# monitor-one-proto-card-v0_0_2.net
KiCad netlist of a schematic drawn in EAGLE
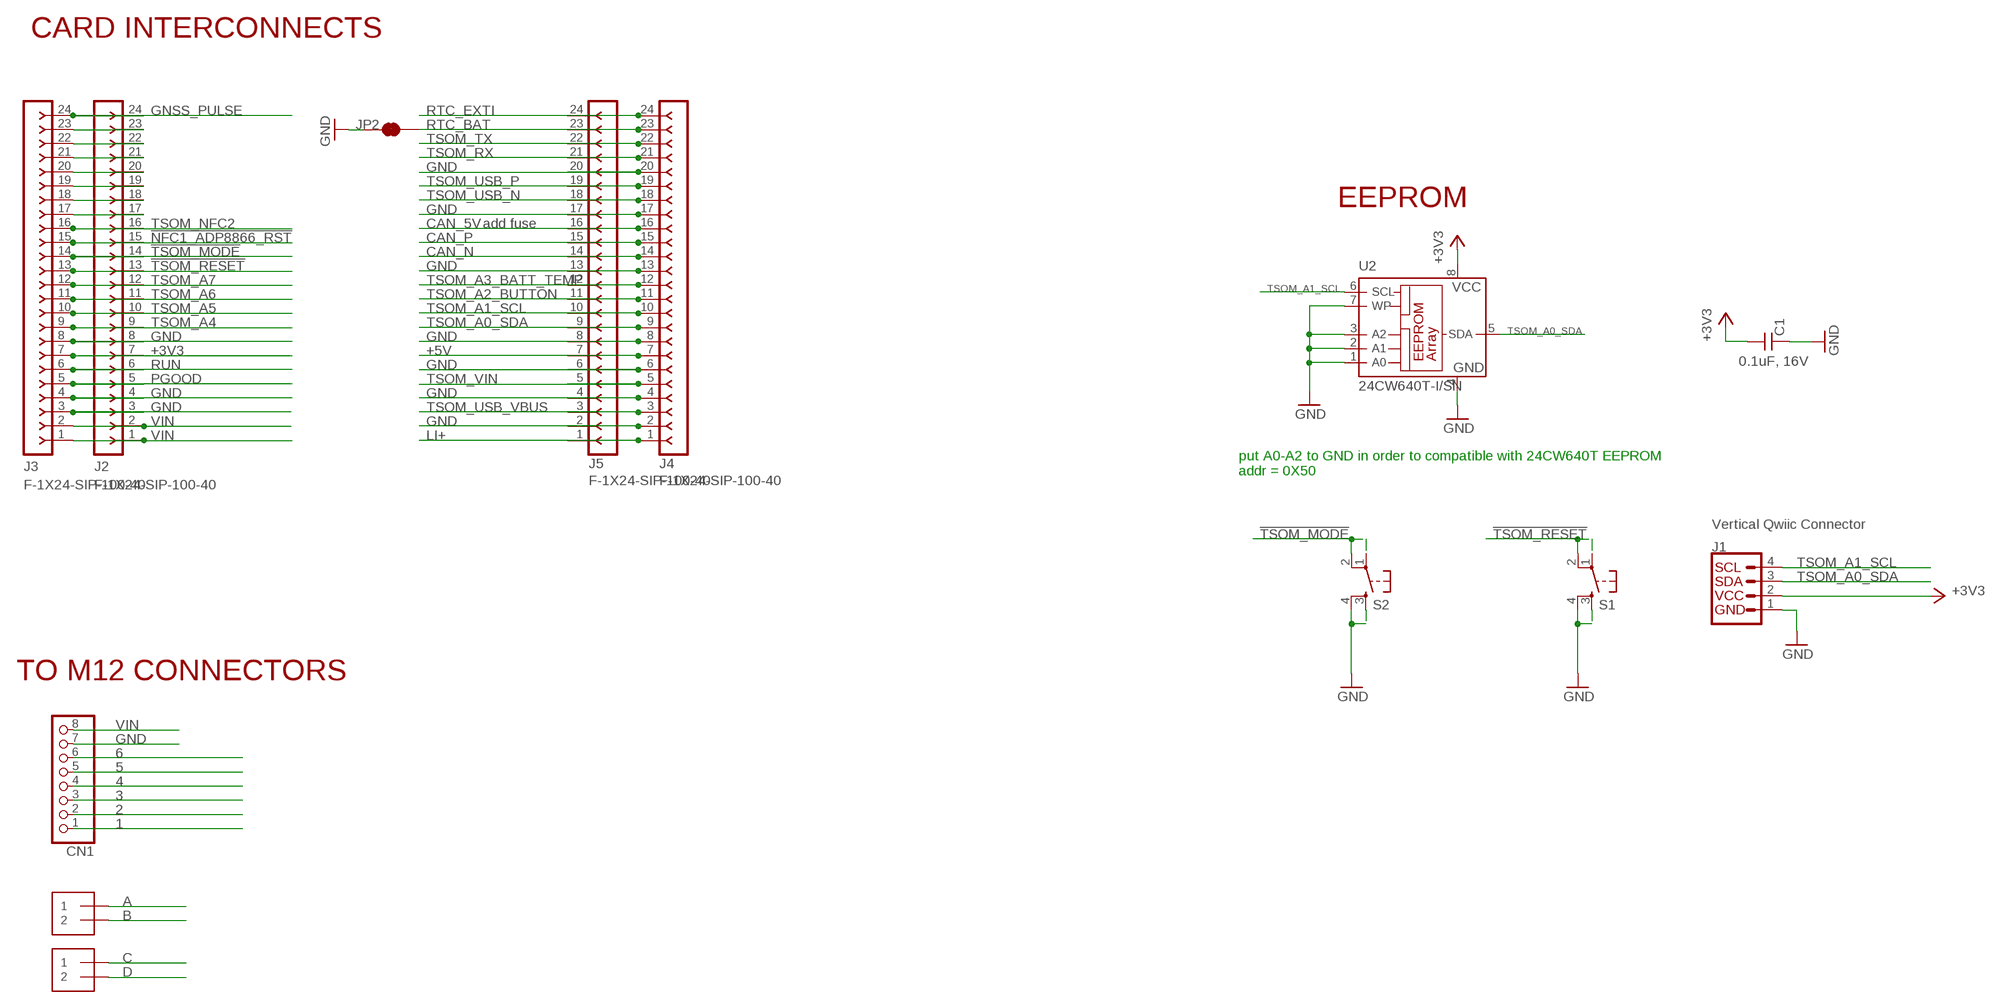
[diagram p0: schematic, sheet 1]

(export (version "E")
  (design (tool "Eeschema 10.0.6"))
  (components
    (comp (ref "C1")
      (value "0.1uF, 16V")
      (footprint "eagle-import:C0603_P")
      (fields (field (name "MFG") "FENGHUA") (field (name "MPN") "0603B104K160NT"))
      (libsource (lib "eagle-import") (part "CAP_06030.1UF_16V_"))
    )
    (comp (ref "CN1")
      (value "JST_8PIN")
      (footprint "eagle-import:JSTPH8")
      (libsource (lib "eagle-import") (part "JST_8PIN"))
    )
    (comp (ref "J1")
      (value "Vertical Qwiic Connector")
      (footprint "eagle-import:JST04_1MM_VERT")
      (libsource (lib "eagle-import") (part "QWIIC_CONNECTOR"))
    )
    (comp (ref "J2")
      (value "F-1X24-SIP-100-40")
      (footprint "eagle-import:SIP-100-24-40")
      (libsource (lib "eagle-import") (part "F-1X24-SIP-100-40"))
    )
    (comp (ref "J3")
      (value "F-1X24-SIP-100-40")
      (footprint "eagle-import:SIP-100-24-40")
      (libsource (lib "eagle-import") (part "F-1X24-SIP-100-40"))
    )
    (comp (ref "J4")
      (value "F-1X24-SIP-100-40")
      (footprint "eagle-import:SIP-100-24-40")
      (libsource (lib "eagle-import") (part "F-1X24-SIP-100-40"))
    )
    (comp (ref "J5")
      (value "F-1X24-SIP-100-40")
      (footprint "eagle-import:SIP-100-24-40")
      (libsource (lib "eagle-import") (part "F-1X24-SIP-100-40"))
    )
    (comp (ref "J8")
      (value "1X2-3.5MM")
      (footprint "eagle-import:1X2-3.5MM")
      (libsource (lib "eagle-import") (part "1X2-3.5MM"))
    )
    (comp (ref "J9")
      (value "1X2-3.5MM")
      (footprint "eagle-import:1X2-3.5MM")
      (libsource (lib "eagle-import") (part "1X2-3.5MM"))
    )
    (comp (ref "JP2")
      (value "JUMPER-SMT_2_NC_TRACE_NO-SILK")
      (footprint "eagle-import:SMT-JUMPER_2_NC_TRACE_NO-SILK")
      (libsource (lib "eagle-import") (part "JUMPER-SMT_2_NC_TRACE_NO-SILK"))
    )
    (comp (ref "S1")
      (value "TAC_SWITCHSMD")
      (footprint "eagle-import:TACTILE_SWITCH_SMD")
      (libsource (lib "eagle-import") (part "TAC_SWITCHSMD"))
    )
    (comp (ref "S2")
      (value "TAC_SWITCHSMD")
      (footprint "eagle-import:TACTILE_SWITCH_SMD")
      (libsource (lib "eagle-import") (part "TAC_SWITCHSMD"))
    )
    (comp (ref "U2")
      (value "24CW640T-I/SN")
      (footprint "eagle-import:SO-08")
      (fields (field (name "MF") "MICROCHIP") (field (name "MPN") "24AA01/SN"))
      (libsource (lib "eagle-import") (part "24SNAA01"))
    )
  )
  (nets
    (net (code "1") (name "+3V3") (class "Default")
      (node (ref "C1") (pin "1") (pinfunction "1_1") (pintype "bidirectional"))
      (node (ref "J1") (pin "2") (pinfunction "2_2") (pintype "power_in"))
      (node (ref "J2") (pin "7") (pinfunction "7_7") (pintype "passive"))
      (node (ref "J3") (pin "7") (pinfunction "7_7") (pintype "passive"))
      (node (ref "U2") (pin "8") (pinfunction "VCC_8") (pintype "power_in"))
    )
    (net (code "2") (name "/+5V") (class "Default")
      (node (ref "J4") (pin "7") (pinfunction "7_7") (pintype "passive"))
      (node (ref "J5") (pin "7") (pinfunction "7_7") (pintype "passive"))
    )
    (net (code "3") (name "/1") (class "Default")
      (node (ref "CN1") (pin "1") (pinfunction "1_1") (pintype "passive"))
    )
    (net (code "4") (name "/2") (class "Default")
      (node (ref "CN1") (pin "2") (pinfunction "2_2") (pintype "passive"))
    )
    (net (code "5") (name "/3") (class "Default")
      (node (ref "CN1") (pin "3") (pinfunction "3_3") (pintype "passive"))
    )
    (net (code "6") (name "/4") (class "Default")
      (node (ref "CN1") (pin "4") (pinfunction "4_4") (pintype "passive"))
    )
    (net (code "7") (name "/5") (class "Default")
      (node (ref "CN1") (pin "5") (pinfunction "5_5") (pintype "passive"))
    )
    (net (code "8") (name "/6") (class "Default")
      (node (ref "CN1") (pin "6") (pinfunction "6_6") (pintype "passive"))
    )
    (net (code "9") (name "/A") (class "Default")
      (node (ref "J8") (pin "1") (pinfunction "1_1") (pintype "passive"))
    )
    (net (code "10") (name "/B") (class "Default")
      (node (ref "J8") (pin "2") (pinfunction "2_2") (pintype "passive"))
    )
    (net (code "11") (name "/C") (class "Default")
      (node (ref "J9") (pin "1") (pinfunction "1_1") (pintype "passive"))
    )
    (net (code "12") (name "/CAN_5V") (class "Default")
      (node (ref "J4") (pin "16") (pinfunction "16_16") (pintype "passive"))
      (node (ref "J5") (pin "16") (pinfunction "16_16") (pintype "passive"))
    )
    (net (code "13") (name "/CAN_N") (class "Default")
      (node (ref "J4") (pin "14") (pinfunction "14_14") (pintype "passive"))
      (node (ref "J5") (pin "14") (pinfunction "14_14") (pintype "passive"))
    )
    (net (code "14") (name "/CAN_P") (class "Default")
      (node (ref "J4") (pin "15") (pinfunction "15_15") (pintype "passive"))
      (node (ref "J5") (pin "15") (pinfunction "15_15") (pintype "passive"))
    )
    (net (code "15") (name "/D") (class "Default")
      (node (ref "J9") (pin "2") (pinfunction "2_2") (pintype "passive"))
    )
    (net (code "16") (name "/GNSS_PULSE") (class "Default")
      (node (ref "J2") (pin "24") (pinfunction "24_24") (pintype "passive"))
      (node (ref "J3") (pin "24") (pinfunction "24_24") (pintype "passive"))
    )
    (net (code "17") (name "/LI+") (class "Default")
      (node (ref "J4") (pin "1") (pinfunction "1_1") (pintype "passive"))
      (node (ref "J5") (pin "1") (pinfunction "1_1") (pintype "passive"))
    )
    (net (code "18") (name "/PGOOD") (class "Default")
      (node (ref "J2") (pin "5") (pinfunction "5_5") (pintype "passive"))
      (node (ref "J3") (pin "5") (pinfunction "5_5") (pintype "passive"))
    )
    (net (code "19") (name "/RTC_BAT") (class "Default")
      (node (ref "J4") (pin "23") (pinfunction "23_23") (pintype "passive"))
      (node (ref "J5") (pin "23") (pinfunction "23_23") (pintype "passive"))
      (node (ref "JP2") (pin "2") (pinfunction "2_2") (pintype "passive"))
    )
    (net (code "20") (name "/RTC_EXTI") (class "Default")
      (node (ref "J4") (pin "24") (pinfunction "24_24") (pintype "passive"))
      (node (ref "J5") (pin "24") (pinfunction "24_24") (pintype "passive"))
    )
    (net (code "21") (name "/RUN") (class "Default")
      (node (ref "J2") (pin "6") (pinfunction "6_6") (pintype "passive"))
      (node (ref "J3") (pin "6") (pinfunction "6_6") (pintype "passive"))
    )
    (net (code "22") (name "/TSOM_A0_SDA") (class "Default")
      (node (ref "J1") (pin "3") (pinfunction "3_3") (pintype "passive"))
      (node (ref "J4") (pin "9") (pinfunction "9_9") (pintype "passive"))
      (node (ref "J5") (pin "9") (pinfunction "9_9") (pintype "passive"))
      (node (ref "U2") (pin "5") (pinfunction "SDA_5") (pintype "bidirectional"))
    )
    (net (code "23") (name "/TSOM_A1_SCL") (class "Default")
      (node (ref "J1") (pin "4") (pinfunction "4_4") (pintype "passive"))
      (node (ref "J4") (pin "10") (pinfunction "10_10") (pintype "passive"))
      (node (ref "J5") (pin "10") (pinfunction "10_10") (pintype "passive"))
      (node (ref "U2") (pin "6") (pinfunction "SCL_6") (pintype "input"))
    )
    (net (code "24") (name "/TSOM_A2_BUTTON") (class "Default")
      (node (ref "J4") (pin "11") (pinfunction "11_11") (pintype "passive"))
      (node (ref "J5") (pin "11") (pinfunction "11_11") (pintype "passive"))
    )
    (net (code "25") (name "/TSOM_A3_BATT_TEMP") (class "Default")
      (node (ref "J4") (pin "12") (pinfunction "12_12") (pintype "passive"))
      (node (ref "J5") (pin "12") (pinfunction "12_12") (pintype "passive"))
    )
    (net (code "26") (name "/TSOM_A4") (class "Default")
      (node (ref "J2") (pin "9") (pinfunction "9_9") (pintype "passive"))
      (node (ref "J3") (pin "9") (pinfunction "9_9") (pintype "passive"))
    )
    (net (code "27") (name "/TSOM_A5") (class "Default")
      (node (ref "J2") (pin "10") (pinfunction "10_10") (pintype "passive"))
      (node (ref "J3") (pin "10") (pinfunction "10_10") (pintype "passive"))
    )
    (net (code "28") (name "/TSOM_A6") (class "Default")
      (node (ref "J2") (pin "11") (pinfunction "11_11") (pintype "passive"))
      (node (ref "J3") (pin "11") (pinfunction "11_11") (pintype "passive"))
    )
    (net (code "29") (name "/TSOM_A7") (class "Default")
      (node (ref "J2") (pin "12") (pinfunction "12_12") (pintype "passive"))
      (node (ref "J3") (pin "12") (pinfunction "12_12") (pintype "passive"))
    )
    (net (code "30") (name "/TSOM_NFC2") (class "Default")
      (node (ref "J2") (pin "16") (pinfunction "16_16") (pintype "passive"))
      (node (ref "J3") (pin "16") (pinfunction "16_16") (pintype "passive"))
    )
    (net (code "31") (name "/TSOM_RX") (class "Default")
      (node (ref "J4") (pin "21") (pinfunction "21_21") (pintype "passive"))
      (node (ref "J5") (pin "21") (pinfunction "21_21") (pintype "passive"))
    )
    (net (code "32") (name "/TSOM_TX") (class "Default")
      (node (ref "J4") (pin "22") (pinfunction "22_22") (pintype "passive"))
      (node (ref "J5") (pin "22") (pinfunction "22_22") (pintype "passive"))
    )
    (net (code "33") (name "/TSOM_USB_N") (class "Default")
      (node (ref "J4") (pin "18") (pinfunction "18_18") (pintype "passive"))
      (node (ref "J5") (pin "18") (pinfunction "18_18") (pintype "passive"))
    )
    (net (code "34") (name "/TSOM_USB_P") (class "Default")
      (node (ref "J4") (pin "19") (pinfunction "19_19") (pintype "passive"))
      (node (ref "J5") (pin "19") (pinfunction "19_19") (pintype "passive"))
    )
    (net (code "35") (name "/TSOM_USB_VBUS") (class "Default")
      (node (ref "J4") (pin "3") (pinfunction "3_3") (pintype "passive"))
      (node (ref "J5") (pin "3") (pinfunction "3_3") (pintype "passive"))
    )
    (net (code "36") (name "/TSOM_VIN") (class "Default")
      (node (ref "J4") (pin "5") (pinfunction "5_5") (pintype "passive"))
      (node (ref "J5") (pin "5") (pinfunction "5_5") (pintype "passive"))
    )
    (net (code "37") (name "/VIN") (class "Default")
      (node (ref "CN1") (pin "8") (pinfunction "8_8") (pintype "passive"))
      (node (ref "J2") (pin "1") (pinfunction "1_1") (pintype "passive"))
      (node (ref "J2") (pin "2") (pinfunction "2_2") (pintype "passive"))
      (node (ref "J3") (pin "1") (pinfunction "1_1") (pintype "passive"))
      (node (ref "J3") (pin "2") (pinfunction "2_2") (pintype "passive"))
    )
    (net (code "38") (name "/~{NFC1_ADP8866_RST}") (class "Default")
      (node (ref "J2") (pin "15") (pinfunction "15_15") (pintype "passive"))
      (node (ref "J3") (pin "15") (pinfunction "15_15") (pintype "passive"))
    )
    (net (code "39") (name "/~{TSOM_MODE}") (class "Default")
      (node (ref "J2") (pin "14") (pinfunction "14_14") (pintype "passive"))
      (node (ref "J3") (pin "14") (pinfunction "14_14") (pintype "passive"))
      (node (ref "S2") (pin "1") (pinfunction "1_1") (pintype "passive"))
      (node (ref "S2") (pin "2") (pinfunction "2_2") (pintype "passive"))
    )
    (net (code "40") (name "/~{TSOM_RESET}") (class "Default")
      (node (ref "J2") (pin "13") (pinfunction "13_13") (pintype "passive"))
      (node (ref "J3") (pin "13") (pinfunction "13_13") (pintype "passive"))
      (node (ref "S1") (pin "1") (pinfunction "1_1") (pintype "passive"))
      (node (ref "S1") (pin "2") (pinfunction "2_2") (pintype "passive"))
    )
    (net (code "41") (name "GND") (class "Default")
      (node (ref "C1") (pin "2") (pinfunction "2_2") (pintype "bidirectional"))
      (node (ref "CN1") (pin "7") (pinfunction "7_7") (pintype "passive"))
      (node (ref "J1") (pin "1") (pinfunction "1_1") (pintype "power_in"))
      (node (ref "J2") (pin "3") (pinfunction "3_3") (pintype "passive"))
      (node (ref "J2") (pin "4") (pinfunction "4_4") (pintype "passive"))
      (node (ref "J2") (pin "8") (pinfunction "8_8") (pintype "passive"))
      (node (ref "J3") (pin "3") (pinfunction "3_3") (pintype "passive"))
      (node (ref "J3") (pin "4") (pinfunction "4_4") (pintype "passive"))
      (node (ref "J3") (pin "8") (pinfunction "8_8") (pintype "passive"))
      (node (ref "J4") (pin "13") (pinfunction "13_13") (pintype "passive"))
      (node (ref "J4") (pin "17") (pinfunction "17_17") (pintype "passive"))
      (node (ref "J4") (pin "2") (pinfunction "2_2") (pintype "passive"))
      (node (ref "J4") (pin "20") (pinfunction "20_20") (pintype "passive"))
      (node (ref "J4") (pin "4") (pinfunction "4_4") (pintype "passive"))
      (node (ref "J4") (pin "6") (pinfunction "6_6") (pintype "passive"))
      (node (ref "J4") (pin "8") (pinfunction "8_8") (pintype "passive"))
      (node (ref "J5") (pin "13") (pinfunction "13_13") (pintype "passive"))
      (node (ref "J5") (pin "17") (pinfunction "17_17") (pintype "passive"))
      (node (ref "J5") (pin "2") (pinfunction "2_2") (pintype "passive"))
      (node (ref "J5") (pin "20") (pinfunction "20_20") (pintype "passive"))
      (node (ref "J5") (pin "4") (pinfunction "4_4") (pintype "passive"))
      (node (ref "J5") (pin "6") (pinfunction "6_6") (pintype "passive"))
      (node (ref "J5") (pin "8") (pinfunction "8_8") (pintype "passive"))
      (node (ref "JP2") (pin "1") (pinfunction "1_1") (pintype "passive"))
      (node (ref "S1") (pin "3") (pinfunction "3_3") (pintype "passive"))
      (node (ref "S1") (pin "4") (pinfunction "4_4") (pintype "passive"))
      (node (ref "S2") (pin "3") (pinfunction "3_3") (pintype "passive"))
      (node (ref "S2") (pin "4") (pinfunction "4_4") (pintype "passive"))
      (node (ref "U2") (pin "1") (pinfunction "A0_1") (pintype "input"))
      (node (ref "U2") (pin "2") (pinfunction "A1_2") (pintype "input"))
      (node (ref "U2") (pin "3") (pinfunction "A2_3") (pintype "input"))
      (node (ref "U2") (pin "4") (pinfunction "GND_4") (pintype "power_in"))
      (node (ref "U2") (pin "7") (pinfunction "WP_7") (pintype "input"))
    )
    (net (code "42") (name "Net-(J2-Pad17)") (class "Default")
      (node (ref "J2") (pin "17") (pinfunction "17_17") (pintype "passive"))
      (node (ref "J3") (pin "17") (pinfunction "17_17") (pintype "passive"))
    )
    (net (code "43") (name "Net-(J2-Pad18)") (class "Default")
      (node (ref "J2") (pin "18") (pinfunction "18_18") (pintype "passive"))
      (node (ref "J3") (pin "18") (pinfunction "18_18") (pintype "passive"))
    )
    (net (code "44") (name "Net-(J2-Pad19)") (class "Default")
      (node (ref "J2") (pin "19") (pinfunction "19_19") (pintype "passive"))
      (node (ref "J3") (pin "19") (pinfunction "19_19") (pintype "passive"))
    )
    (net (code "45") (name "Net-(J2-Pad20)") (class "Default")
      (node (ref "J2") (pin "20") (pinfunction "20_20") (pintype "passive"))
      (node (ref "J3") (pin "20") (pinfunction "20_20") (pintype "passive"))
    )
    (net (code "46") (name "Net-(J2-Pad21)") (class "Default")
      (node (ref "J2") (pin "21") (pinfunction "21_21") (pintype "passive"))
      (node (ref "J3") (pin "21") (pinfunction "21_21") (pintype "passive"))
    )
    (net (code "47") (name "Net-(J2-Pad22)") (class "Default")
      (node (ref "J2") (pin "22") (pinfunction "22_22") (pintype "passive"))
      (node (ref "J3") (pin "22") (pinfunction "22_22") (pintype "passive"))
    )
    (net (code "48") (name "Net-(J2-Pad23)") (class "Default")
      (node (ref "J2") (pin "23") (pinfunction "23_23") (pintype "passive"))
      (node (ref "J3") (pin "23") (pinfunction "23_23") (pintype "passive"))
    )
  )
)
